# JST_charging.net
KiCad netlist of a schematic drawn in EAGLE
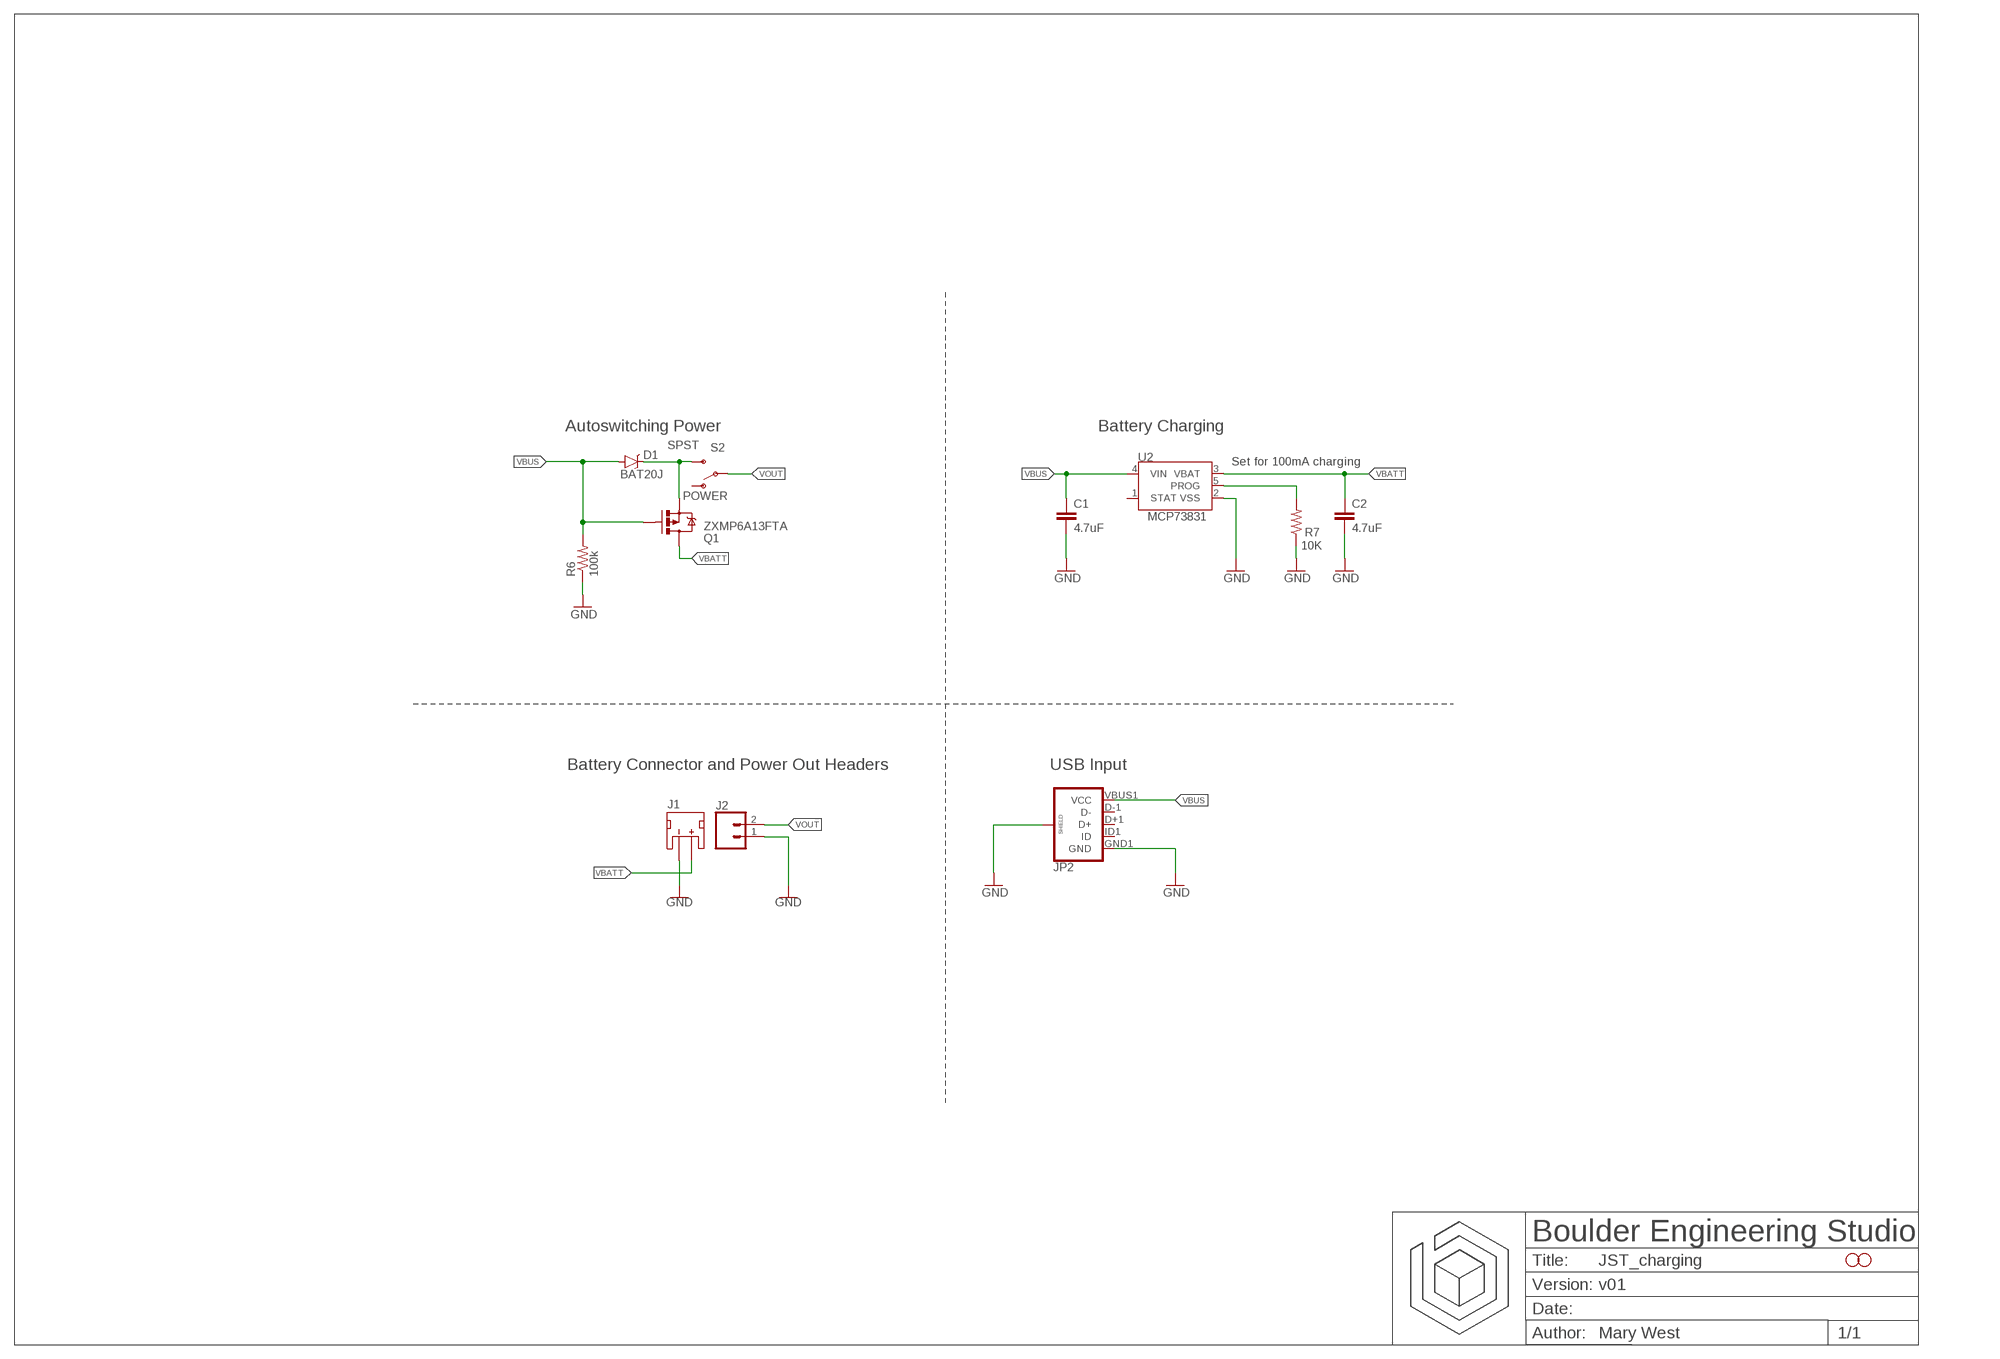
[diagram p0: schematic, sheet 1]

(export (version "E")
  (design (tool "Eeschema 10.0.6"))
  (components
    (comp (ref "C1")
      (value "4.7uF")
      (footprint "eagle-import:0603-CAP")
      (libsource (lib "eagle-import") (part "CAP0603-CAP"))
    )
    (comp (ref "C2")
      (value "4.7uF")
      (footprint "eagle-import:0603-CAP")
      (libsource (lib "eagle-import") (part "CAP0603-CAP"))
    )
    (comp (ref "D1")
      (value "BAT20J")
      (footprint "eagle-import:SOD-323")
      (libsource (lib "eagle-import") (part "DIODE-SCHOTTKY-BAT20J"))
    )
    (comp (ref "H1")
      (value "STAND-OFFTIGHT")
      (footprint "eagle-import:STAND-OFF-TIGHT")
      (libsource (lib "eagle-import") (part "STAND-OFFTIGHT"))
    )
    (comp (ref "H2")
      (value "STAND-OFFTIGHT")
      (footprint "eagle-import:STAND-OFF-TIGHT")
      (libsource (lib "eagle-import") (part "STAND-OFFTIGHT"))
    )
    (comp (ref "J1")
      (value "JST_2MM_MALE")
      (footprint "eagle-import:JST-2-SMD")
      (libsource (lib "eagle-import") (part "JST_2MM_MALE"))
    )
    (comp (ref "J2")
      (value "CONN_021X02_NO_SILK")
      (footprint "eagle-import:1X02_NO_SILK")
      (libsource (lib "eagle-import") (part "CONN_021X02_NO_SILK"))
    )
    (comp (ref "JP2")
      (value "USB_MICROB_PLUGCONN-11752")
      (footprint "eagle-import:USB-B-MICRO-SMD_V03")
      (libsource (lib "eagle-import") (part "USB_MICROB_PLUGCONN-11752"))
    )
    (comp (ref "Q1")
      (value "ZXMP6A13FTA")
      (footprint "eagle-import:SOT23-3")
      (libsource (lib "eagle-import") (part "MOSFET-PCHANNEL"))
    )
    (comp (ref "R6")
      (value "100k")
      (footprint "eagle-import:0603-RES")
      (libsource (lib "eagle-import") (part "100KOHM-1/10W-1%(0603)"))
    )
    (comp (ref "R7")
      (value "10K")
      (footprint "eagle-import:0603-RES")
      (libsource (lib "eagle-import") (part "10KOHM-1/10W-1%(0603)0603"))
    )
    (comp (ref "S2")
      (value "POWER")
      (footprint "eagle-import:SWITCH-SPST-SMD-A")
      (libsource (lib "eagle-import") (part "SWITCH-SPDT-SMD-A"))
    )
    (comp (ref "U2")
      (value "MCP73831")
      (footprint "eagle-import:SOT23-5")
      (libsource (lib "eagle-import") (part "MCP73831"))
    )
  )
  (nets
    (net (code "1") (name "GND") (class "Default")
      (node (ref "C1") (pin "2") (pinfunction "2_2") (pintype "passive"))
      (node (ref "C2") (pin "2") (pinfunction "2_2") (pintype "passive"))
      (node (ref "J1") (pin "1") (pinfunction "-_1") (pintype "bidirectional"))
      (node (ref "J2") (pin "1") (pinfunction "1_1") (pintype "passive"))
      (node (ref "JP2") (pin "GND1") (pinfunction "GND_GND1") (pintype "bidirectional"))
      (node (ref "JP2") (pin "SHIELD1") (pinfunction "SHIELD_SHIELD1") (pintype "bidirectional"))
      (node (ref "JP2") (pin "SHIELD2") (pinfunction "SHIELD_SHIELD2") (pintype "bidirectional"))
      (node (ref "JP2") (pin "SHIELD3") (pinfunction "SHIELD_SHIELD3") (pintype "bidirectional"))
      (node (ref "R6") (pin "1") (pinfunction "1_1") (pintype "passive"))
      (node (ref "R7") (pin "1") (pinfunction "1_1") (pintype "passive"))
      (node (ref "U2") (pin "2") (pinfunction "VSS_2") (pintype "power_in"))
    )
    (net (code "2") (name "Net-(Q1-S)") (class "Default")
      (node (ref "D1") (pin "C") (pinfunction "C_C") (pintype "passive"))
      (node (ref "Q1") (pin "2") (pinfunction "S_2") (pintype "passive"))
      (node (ref "S2") (pin "3") (pinfunction "S_3") (pintype "passive"))
    )
    (net (code "3") (name "Net-(U2-PROG)") (class "Default")
      (node (ref "R7") (pin "2") (pinfunction "2_2") (pintype "passive"))
      (node (ref "U2") (pin "5") (pinfunction "PROG_5") (pintype "input"))
    )
    (net (code "4") (name "VBATT") (class "Default")
      (node (ref "C2") (pin "1") (pinfunction "1_1") (pintype "passive"))
      (node (ref "J1") (pin "2") (pinfunction "+_2") (pintype "bidirectional"))
      (node (ref "Q1") (pin "3") (pinfunction "D_3") (pintype "passive"))
      (node (ref "U2") (pin "3") (pinfunction "VBAT_3") (pintype "power_in"))
    )
    (net (code "5") (name "VBUS") (class "Default")
      (node (ref "C1") (pin "1") (pinfunction "1_1") (pintype "passive"))
      (node (ref "D1") (pin "A") (pinfunction "A_A") (pintype "passive"))
      (node (ref "JP2") (pin "VBUS1") (pinfunction "VCC_VBUS1") (pintype "bidirectional"))
      (node (ref "Q1") (pin "1") (pinfunction "G_1") (pintype "passive"))
      (node (ref "R6") (pin "2") (pinfunction "2_2") (pintype "passive"))
      (node (ref "U2") (pin "4") (pinfunction "VIN_4") (pintype "power_in"))
    )
    (net (code "6") (name "VOUT") (class "Default")
      (node (ref "J2") (pin "2") (pinfunction "2_2") (pintype "passive"))
      (node (ref "S2") (pin "2") (pinfunction "P_2") (pintype "passive"))
    )
    (net (code "7") (name "unconnected-(J1-PAD1-PadNC1)") (class "Default")
      (node (ref "J1") (pin "NC1") (pinfunction "PAD1_NC1") (pintype "bidirectional"))
    )
    (net (code "8") (name "unconnected-(J1-PAD2-PadNC2)") (class "Default")
      (node (ref "J1") (pin "NC2") (pinfunction "PAD2_NC2") (pintype "bidirectional"))
    )
    (net (code "9") (name "unconnected-(JP2-D+-PadD+1)") (class "Default")
      (node (ref "JP2") (pin "D+1") (pinfunction "D+_D+1") (pintype "bidirectional"))
    )
    (net (code "10") (name "unconnected-(JP2-D--PadD-1)") (class "Default")
      (node (ref "JP2") (pin "D-1") (pinfunction "D-_D-1") (pintype "bidirectional"))
    )
    (net (code "11") (name "unconnected-(JP2-ID-PadID1)") (class "Default")
      (node (ref "JP2") (pin "ID1") (pinfunction "ID_ID1") (pintype "bidirectional"))
    )
    (net (code "12") (name "unconnected-(S2-O-Pad1)") (class "Default")
      (node (ref "S2") (pin "1") (pinfunction "O_1") (pintype "passive"))
    )
    (net (code "13") (name "unconnected-(U2-STAT-Pad1)") (class "Default")
      (node (ref "U2") (pin "1") (pinfunction "STAT_1") (pintype "output"))
    )
  )
)
